# FSKmodem2.net
KiCad netlist of a schematic drawn in EAGLE
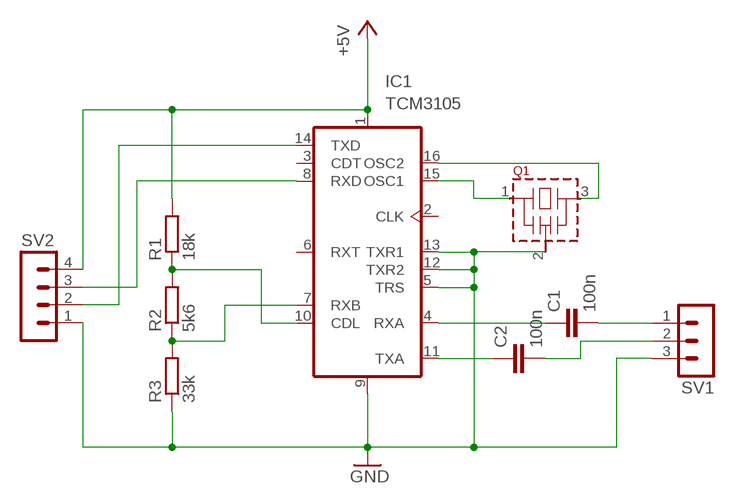
[diagram p0: schematic, sheet 1]

(export (version "E")
  (design (tool "Eeschema 10.0.6"))
  (components
    (comp (ref "C1")
      (value "100n")
      (footprint "eagle-import:C050-024X044")
      (libsource (lib "eagle-import") (part "C-EU050-024X044"))
    )
    (comp (ref "C2")
      (value "100n")
      (footprint "eagle-import:C050-024X044")
      (libsource (lib "eagle-import") (part "C-EU050-024X044"))
    )
    (comp (ref "IC1")
      (value "TCM3105")
      (footprint "eagle-import:DIL16")
      (libsource (lib "eagle-import") (part "TCM3105"))
    )
    (comp (ref "Q1")
      (value "CSTLS_G")
      (footprint "eagle-import:CSTLS_G9")
      (libsource (lib "eagle-import") (part "murata-resonators_CSTLS_G"))
    )
    (comp (ref "R1")
      (value "18k")
      (footprint "eagle-import:0204_5")
      (libsource (lib "eagle-import") (part "R-EU_0204/5"))
    )
    (comp (ref "R2")
      (value "5k6")
      (footprint "eagle-import:0204_5")
      (libsource (lib "eagle-import") (part "R-EU_0204/5"))
    )
    (comp (ref "R3")
      (value "33k")
      (footprint "eagle-import:0204_5")
      (libsource (lib "eagle-import") (part "R-EU_0204/5"))
    )
    (comp (ref "SV1")
      (value "MA03-1")
      (footprint "eagle-import:MA03-1")
      (libsource (lib "eagle-import") (part "MA03-1"))
    )
    (comp (ref "SV2")
      (value "MA04-1")
      (footprint "eagle-import:MA04-1")
      (libsource (lib "eagle-import") (part "MA04-1"))
    )
  )
  (nets
    (net (code "1") (name "+5V") (class "Default")
      (node (ref "IC1") (pin "1") (pinfunction "VDD_1") (pintype "power_in"))
      (node (ref "R1") (pin "2") (pinfunction "2_2") (pintype "passive"))
      (node (ref "SV2") (pin "4") (pinfunction "4_4") (pintype "passive"))
    )
    (net (code "2") (name "GND") (class "Default")
      (node (ref "IC1") (pin "12") (pinfunction "TXR2_12") (pintype "input"))
      (node (ref "IC1") (pin "13") (pinfunction "TXR1_13") (pintype "input"))
      (node (ref "IC1") (pin "5") (pinfunction "TRS_5") (pintype "input"))
      (node (ref "IC1") (pin "9") (pinfunction "VSS_9") (pintype "power_in"))
      (node (ref "Q1") (pin "2") (pinfunction "VSS_2") (pintype "power_in"))
      (node (ref "R3") (pin "1") (pinfunction "1_1") (pintype "passive"))
      (node (ref "SV1") (pin "3") (pinfunction "3_3") (pintype "passive"))
      (node (ref "SV2") (pin "1") (pinfunction "1_1") (pintype "passive"))
    )
    (net (code "3") (name "Net-(C1-Pad2)") (class "Default")
      (node (ref "C1") (pin "2") (pinfunction "2_2") (pintype "passive"))
      (node (ref "SV1") (pin "1") (pinfunction "1_1") (pintype "passive"))
    )
    (net (code "4") (name "Net-(C2-Pad2)") (class "Default")
      (node (ref "C2") (pin "2") (pinfunction "2_2") (pintype "passive"))
      (node (ref "SV1") (pin "2") (pinfunction "2_2") (pintype "passive"))
    )
    (net (code "5") (name "Net-(IC1-CDL)") (class "Default")
      (node (ref "IC1") (pin "10") (pinfunction "CDL_10") (pintype "bidirectional"))
      (node (ref "R1") (pin "1") (pinfunction "1_1") (pintype "passive"))
      (node (ref "R2") (pin "2") (pinfunction "2_2") (pintype "passive"))
    )
    (net (code "6") (name "Net-(IC1-OSC1)") (class "Default")
      (node (ref "IC1") (pin "15") (pinfunction "OSC1_15") (pintype "bidirectional"))
      (node (ref "Q1") (pin "1") (pinfunction "1_1") (pintype "output"))
    )
    (net (code "7") (name "Net-(IC1-OSC2)") (class "Default")
      (node (ref "IC1") (pin "16") (pinfunction "OSC2_16") (pintype "bidirectional"))
      (node (ref "Q1") (pin "3") (pinfunction "3_3") (pintype "input"))
    )
    (net (code "8") (name "Net-(IC1-RXA)") (class "Default")
      (node (ref "C1") (pin "1") (pinfunction "1_1") (pintype "passive"))
      (node (ref "IC1") (pin "4") (pinfunction "RXA_4") (pintype "input"))
    )
    (net (code "9") (name "Net-(IC1-RXB)") (class "Default")
      (node (ref "IC1") (pin "7") (pinfunction "RXB_7") (pintype "bidirectional"))
      (node (ref "R2") (pin "1") (pinfunction "1_1") (pintype "passive"))
      (node (ref "R3") (pin "2") (pinfunction "2_2") (pintype "passive"))
    )
    (net (code "10") (name "Net-(IC1-RXD)") (class "Default")
      (node (ref "IC1") (pin "8") (pinfunction "RXD_8") (pintype "output"))
      (node (ref "SV2") (pin "3") (pinfunction "3_3") (pintype "passive"))
    )
    (net (code "11") (name "Net-(IC1-TXA)") (class "Default")
      (node (ref "C2") (pin "1") (pinfunction "1_1") (pintype "passive"))
      (node (ref "IC1") (pin "11") (pinfunction "TXA_11") (pintype "output"))
    )
    (net (code "12") (name "Net-(IC1-TXD)") (class "Default")
      (node (ref "IC1") (pin "14") (pinfunction "TXD_14") (pintype "input"))
      (node (ref "SV2") (pin "2") (pinfunction "2_2") (pintype "passive"))
    )
    (net (code "13") (name "unconnected-(IC1-CDT-Pad3)") (class "Default")
      (node (ref "IC1") (pin "3") (pinfunction "CDT_3") (pintype "output"))
    )
    (net (code "14") (name "unconnected-(IC1-CLK-Pad2)") (class "Default")
      (node (ref "IC1") (pin "2") (pinfunction "CLK_2") (pintype "output"))
    )
    (net (code "15") (name "unconnected-(IC1-RXT-Pad6)") (class "Default")
      (node (ref "IC1") (pin "6") (pinfunction "RXT_6") (pintype "bidirectional"))
    )
  )
)
